# placa.net
KiCad netlist of a schematic drawn in EAGLE
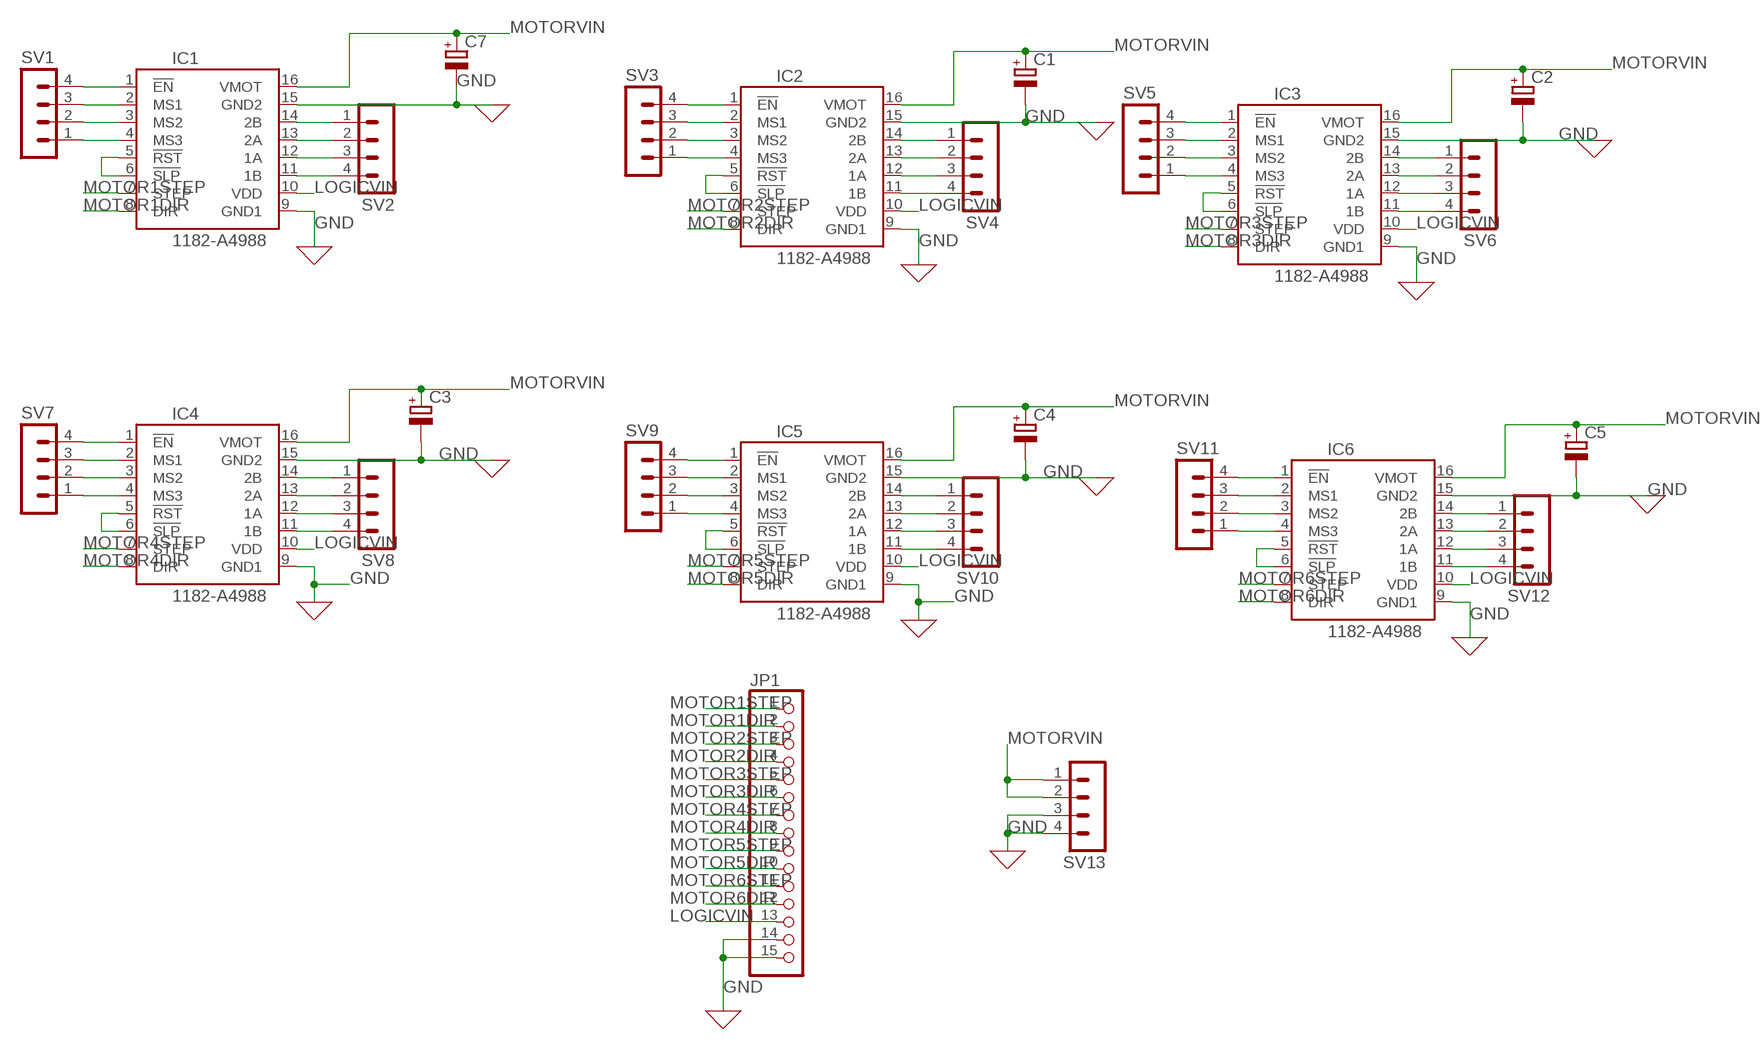
[diagram p0: schematic, sheet 1]

(export (version "E")
  (design (tool "Eeschema 10.0.6"))
  (components
    (comp (ref "C1")
      (value "CPOL-EUE2.5-7")
      (footprint "eagle-import:E2,5-7")
      (libsource (lib "eagle-import") (part "CPOL-EUE2.5-7"))
    )
    (comp (ref "C2")
      (value "CPOL-EUE2.5-7")
      (footprint "eagle-import:E2,5-7")
      (libsource (lib "eagle-import") (part "CPOL-EUE2.5-7"))
    )
    (comp (ref "C3")
      (value "CPOL-EUE2.5-7")
      (footprint "eagle-import:E2,5-7")
      (libsource (lib "eagle-import") (part "CPOL-EUE2.5-7"))
    )
    (comp (ref "C4")
      (value "CPOL-EUE2.5-7")
      (footprint "eagle-import:E2,5-7")
      (libsource (lib "eagle-import") (part "CPOL-EUE2.5-7"))
    )
    (comp (ref "C5")
      (value "CPOL-EUE2.5-7")
      (footprint "eagle-import:E2,5-7")
      (libsource (lib "eagle-import") (part "CPOL-EUE2.5-7"))
    )
    (comp (ref "C7")
      (value "CPOL-EUE2.5-7")
      (footprint "eagle-import:E2,5-7")
      (libsource (lib "eagle-import") (part "CPOL-EUE2.5-7"))
    )
    (comp (ref "IC1")
      (value "1182-A4988")
      (footprint "eagle-import:A4988")
      (libsource (lib "eagle-import") (part "1182-A4988"))
    )
    (comp (ref "IC2")
      (value "1182-A4988")
      (footprint "eagle-import:A4988")
      (libsource (lib "eagle-import") (part "1182-A4988"))
    )
    (comp (ref "IC3")
      (value "1182-A4988")
      (footprint "eagle-import:A4988")
      (libsource (lib "eagle-import") (part "1182-A4988"))
    )
    (comp (ref "IC4")
      (value "1182-A4988")
      (footprint "eagle-import:A4988")
      (libsource (lib "eagle-import") (part "1182-A4988"))
    )
    (comp (ref "IC5")
      (value "1182-A4988")
      (footprint "eagle-import:A4988")
      (libsource (lib "eagle-import") (part "1182-A4988"))
    )
    (comp (ref "IC6")
      (value "1182-A4988")
      (footprint "eagle-import:A4988")
      (libsource (lib "eagle-import") (part "1182-A4988"))
    )
    (comp (ref "JP1")
      (value "PINHD-1X15")
      (footprint "eagle-import:1X15")
      (libsource (lib "eagle-import") (part "PINHD-1X15"))
    )
    (comp (ref "SV1")
      (value "MA04-1")
      (footprint "eagle-import:MA04-1")
      (libsource (lib "eagle-import") (part "MA04-1"))
    )
    (comp (ref "SV2")
      (value "MA04-1")
      (footprint "eagle-import:MA04-1")
      (libsource (lib "eagle-import") (part "MA04-1"))
    )
    (comp (ref "SV3")
      (value "MA04-1")
      (footprint "eagle-import:MA04-1")
      (libsource (lib "eagle-import") (part "MA04-1"))
    )
    (comp (ref "SV4")
      (value "MA04-1")
      (footprint "eagle-import:MA04-1")
      (libsource (lib "eagle-import") (part "MA04-1"))
    )
    (comp (ref "SV5")
      (value "MA04-1")
      (footprint "eagle-import:MA04-1")
      (libsource (lib "eagle-import") (part "MA04-1"))
    )
    (comp (ref "SV6")
      (value "MA04-1")
      (footprint "eagle-import:MA04-1")
      (libsource (lib "eagle-import") (part "MA04-1"))
    )
    (comp (ref "SV7")
      (value "MA04-1")
      (footprint "eagle-import:MA04-1")
      (libsource (lib "eagle-import") (part "MA04-1"))
    )
    (comp (ref "SV8")
      (value "MA04-1")
      (footprint "eagle-import:MA04-1")
      (libsource (lib "eagle-import") (part "MA04-1"))
    )
    (comp (ref "SV9")
      (value "MA04-1")
      (footprint "eagle-import:MA04-1")
      (libsource (lib "eagle-import") (part "MA04-1"))
    )
    (comp (ref "SV10")
      (value "MA04-1")
      (footprint "eagle-import:MA04-1")
      (libsource (lib "eagle-import") (part "MA04-1"))
    )
    (comp (ref "SV11")
      (value "MA04-1")
      (footprint "eagle-import:MA04-1")
      (libsource (lib "eagle-import") (part "MA04-1"))
    )
    (comp (ref "SV12")
      (value "MA04-1")
      (footprint "eagle-import:MA04-1")
      (libsource (lib "eagle-import") (part "MA04-1"))
    )
    (comp (ref "SV13")
      (value "MA04-1")
      (footprint "eagle-import:MA04-1")
      (libsource (lib "eagle-import") (part "MA04-1"))
    )
  )
  (nets
    (net (code "1") (name "/LOGICVIN") (class "Default")
      (node (ref "IC1") (pin "10") (pinfunction "VDD_10") (pintype "power_in"))
      (node (ref "IC2") (pin "10") (pinfunction "VDD_10") (pintype "power_in"))
      (node (ref "IC3") (pin "10") (pinfunction "VDD_10") (pintype "power_in"))
      (node (ref "IC4") (pin "10") (pinfunction "VDD_10") (pintype "power_in"))
      (node (ref "IC5") (pin "10") (pinfunction "VDD_10") (pintype "power_in"))
      (node (ref "IC6") (pin "10") (pinfunction "VDD_10") (pintype "power_in"))
      (node (ref "JP1") (pin "13") (pinfunction "13_13") (pintype "passive"))
    )
    (net (code "2") (name "/MOTOR1DIR") (class "Default")
      (node (ref "IC1") (pin "8") (pinfunction "DIR_8") (pintype "input"))
      (node (ref "JP1") (pin "2") (pinfunction "2_2") (pintype "passive"))
    )
    (net (code "3") (name "/MOTOR1STEP") (class "Default")
      (node (ref "IC1") (pin "7") (pinfunction "STEP_7") (pintype "input"))
      (node (ref "JP1") (pin "1") (pinfunction "1_1") (pintype "passive"))
    )
    (net (code "4") (name "/MOTOR2DIR") (class "Default")
      (node (ref "IC2") (pin "8") (pinfunction "DIR_8") (pintype "input"))
      (node (ref "JP1") (pin "4") (pinfunction "4_4") (pintype "passive"))
    )
    (net (code "5") (name "/MOTOR2STEP") (class "Default")
      (node (ref "IC2") (pin "7") (pinfunction "STEP_7") (pintype "input"))
      (node (ref "JP1") (pin "3") (pinfunction "3_3") (pintype "passive"))
    )
    (net (code "6") (name "/MOTOR3DIR") (class "Default")
      (node (ref "IC3") (pin "8") (pinfunction "DIR_8") (pintype "input"))
      (node (ref "JP1") (pin "6") (pinfunction "6_6") (pintype "passive"))
    )
    (net (code "7") (name "/MOTOR3STEP") (class "Default")
      (node (ref "IC3") (pin "7") (pinfunction "STEP_7") (pintype "input"))
      (node (ref "JP1") (pin "5") (pinfunction "5_5") (pintype "passive"))
    )
    (net (code "8") (name "/MOTOR4DIR") (class "Default")
      (node (ref "IC4") (pin "8") (pinfunction "DIR_8") (pintype "input"))
      (node (ref "JP1") (pin "8") (pinfunction "8_8") (pintype "passive"))
    )
    (net (code "9") (name "/MOTOR4STEP") (class "Default")
      (node (ref "IC4") (pin "7") (pinfunction "STEP_7") (pintype "input"))
      (node (ref "JP1") (pin "7") (pinfunction "7_7") (pintype "passive"))
    )
    (net (code "10") (name "/MOTOR5DIR") (class "Default")
      (node (ref "IC5") (pin "8") (pinfunction "DIR_8") (pintype "input"))
      (node (ref "JP1") (pin "10") (pinfunction "10_10") (pintype "passive"))
    )
    (net (code "11") (name "/MOTOR5STEP") (class "Default")
      (node (ref "IC5") (pin "7") (pinfunction "STEP_7") (pintype "input"))
      (node (ref "JP1") (pin "9") (pinfunction "9_9") (pintype "passive"))
    )
    (net (code "12") (name "/MOTOR6DIR") (class "Default")
      (node (ref "IC6") (pin "8") (pinfunction "DIR_8") (pintype "input"))
      (node (ref "JP1") (pin "12") (pinfunction "12_12") (pintype "passive"))
    )
    (net (code "13") (name "/MOTOR6STEP") (class "Default")
      (node (ref "IC6") (pin "7") (pinfunction "STEP_7") (pintype "input"))
      (node (ref "JP1") (pin "11") (pinfunction "11_11") (pintype "passive"))
    )
    (net (code "14") (name "/MOTORVIN") (class "Default")
      (node (ref "C1") (pin "+") (pinfunction "+_+") (pintype "passive"))
      (node (ref "C2") (pin "+") (pinfunction "+_+") (pintype "passive"))
      (node (ref "C3") (pin "+") (pinfunction "+_+") (pintype "passive"))
      (node (ref "C4") (pin "+") (pinfunction "+_+") (pintype "passive"))
      (node (ref "C5") (pin "+") (pinfunction "+_+") (pintype "passive"))
      (node (ref "C7") (pin "+") (pinfunction "+_+") (pintype "passive"))
      (node (ref "IC1") (pin "16") (pinfunction "VMOT_16") (pintype "power_in"))
      (node (ref "IC2") (pin "16") (pinfunction "VMOT_16") (pintype "power_in"))
      (node (ref "IC3") (pin "16") (pinfunction "VMOT_16") (pintype "power_in"))
      (node (ref "IC4") (pin "16") (pinfunction "VMOT_16") (pintype "power_in"))
      (node (ref "IC5") (pin "16") (pinfunction "VMOT_16") (pintype "power_in"))
      (node (ref "IC6") (pin "16") (pinfunction "VMOT_16") (pintype "power_in"))
      (node (ref "SV13") (pin "1") (pinfunction "1_1") (pintype "passive"))
      (node (ref "SV13") (pin "2") (pinfunction "2_2") (pintype "passive"))
    )
    (net (code "15") (name "GND") (class "Default")
      (node (ref "C1") (pin "-") (pinfunction "-_-") (pintype "passive"))
      (node (ref "C2") (pin "-") (pinfunction "-_-") (pintype "passive"))
      (node (ref "C3") (pin "-") (pinfunction "-_-") (pintype "passive"))
      (node (ref "C4") (pin "-") (pinfunction "-_-") (pintype "passive"))
      (node (ref "C5") (pin "-") (pinfunction "-_-") (pintype "passive"))
      (node (ref "C7") (pin "-") (pinfunction "-_-") (pintype "passive"))
      (node (ref "IC1") (pin "15") (pinfunction "GND2_15") (pintype "power_in"))
      (node (ref "IC1") (pin "9") (pinfunction "GND1_9") (pintype "power_in"))
      (node (ref "IC2") (pin "15") (pinfunction "GND2_15") (pintype "power_in"))
      (node (ref "IC2") (pin "9") (pinfunction "GND1_9") (pintype "power_in"))
      (node (ref "IC3") (pin "15") (pinfunction "GND2_15") (pintype "power_in"))
      (node (ref "IC3") (pin "9") (pinfunction "GND1_9") (pintype "power_in"))
      (node (ref "IC4") (pin "15") (pinfunction "GND2_15") (pintype "power_in"))
      (node (ref "IC4") (pin "9") (pinfunction "GND1_9") (pintype "power_in"))
      (node (ref "IC5") (pin "15") (pinfunction "GND2_15") (pintype "power_in"))
      (node (ref "IC5") (pin "9") (pinfunction "GND1_9") (pintype "power_in"))
      (node (ref "IC6") (pin "15") (pinfunction "GND2_15") (pintype "power_in"))
      (node (ref "IC6") (pin "9") (pinfunction "GND1_9") (pintype "power_in"))
      (node (ref "JP1") (pin "14") (pinfunction "14_14") (pintype "passive"))
      (node (ref "JP1") (pin "15") (pinfunction "15_15") (pintype "passive"))
      (node (ref "SV13") (pin "3") (pinfunction "3_3") (pintype "passive"))
      (node (ref "SV13") (pin "4") (pinfunction "4_4") (pintype "passive"))
    )
    (net (code "16") (name "Net-(IC1-1A)") (class "Default")
      (node (ref "IC1") (pin "12") (pinfunction "1A_12") (pintype "output"))
      (node (ref "SV2") (pin "3") (pinfunction "3_3") (pintype "passive"))
    )
    (net (code "17") (name "Net-(IC1-1B)") (class "Default")
      (node (ref "IC1") (pin "11") (pinfunction "1B_11") (pintype "output"))
      (node (ref "SV2") (pin "4") (pinfunction "4_4") (pintype "passive"))
    )
    (net (code "18") (name "Net-(IC1-2A)") (class "Default")
      (node (ref "IC1") (pin "13") (pinfunction "2A_13") (pintype "output"))
      (node (ref "SV2") (pin "2") (pinfunction "2_2") (pintype "passive"))
    )
    (net (code "19") (name "Net-(IC1-2B)") (class "Default")
      (node (ref "IC1") (pin "14") (pinfunction "2B_14") (pintype "output"))
      (node (ref "SV2") (pin "1") (pinfunction "1_1") (pintype "passive"))
    )
    (net (code "20") (name "Net-(IC1-MS1)") (class "Default")
      (node (ref "IC1") (pin "2") (pinfunction "MS1_2") (pintype "passive"))
      (node (ref "SV1") (pin "3") (pinfunction "3_3") (pintype "passive"))
    )
    (net (code "21") (name "Net-(IC1-MS2)") (class "Default")
      (node (ref "IC1") (pin "3") (pinfunction "MS2_3") (pintype "passive"))
      (node (ref "SV1") (pin "2") (pinfunction "2_2") (pintype "passive"))
    )
    (net (code "22") (name "Net-(IC1-MS3)") (class "Default")
      (node (ref "IC1") (pin "4") (pinfunction "MS3_4") (pintype "passive"))
      (node (ref "SV1") (pin "1") (pinfunction "1_1") (pintype "passive"))
    )
    (net (code "23") (name "Net-(IC1-~{EN})") (class "Default")
      (node (ref "IC1") (pin "1") (pinfunction "~{EN}_1") (pintype "passive"))
      (node (ref "SV1") (pin "4") (pinfunction "4_4") (pintype "passive"))
    )
    (net (code "24") (name "Net-(IC1-~{RST})") (class "Default")
      (node (ref "IC1") (pin "5") (pinfunction "~{RST}_5") (pintype "passive"))
      (node (ref "IC1") (pin "6") (pinfunction "~{SLP}_6") (pintype "passive"))
    )
    (net (code "25") (name "Net-(IC2-1A)") (class "Default")
      (node (ref "IC2") (pin "12") (pinfunction "1A_12") (pintype "output"))
      (node (ref "SV4") (pin "3") (pinfunction "3_3") (pintype "passive"))
    )
    (net (code "26") (name "Net-(IC2-1B)") (class "Default")
      (node (ref "IC2") (pin "11") (pinfunction "1B_11") (pintype "output"))
      (node (ref "SV4") (pin "4") (pinfunction "4_4") (pintype "passive"))
    )
    (net (code "27") (name "Net-(IC2-2A)") (class "Default")
      (node (ref "IC2") (pin "13") (pinfunction "2A_13") (pintype "output"))
      (node (ref "SV4") (pin "2") (pinfunction "2_2") (pintype "passive"))
    )
    (net (code "28") (name "Net-(IC2-2B)") (class "Default")
      (node (ref "IC2") (pin "14") (pinfunction "2B_14") (pintype "output"))
      (node (ref "SV4") (pin "1") (pinfunction "1_1") (pintype "passive"))
    )
    (net (code "29") (name "Net-(IC2-MS1)") (class "Default")
      (node (ref "IC2") (pin "2") (pinfunction "MS1_2") (pintype "passive"))
      (node (ref "SV3") (pin "3") (pinfunction "3_3") (pintype "passive"))
    )
    (net (code "30") (name "Net-(IC2-MS2)") (class "Default")
      (node (ref "IC2") (pin "3") (pinfunction "MS2_3") (pintype "passive"))
      (node (ref "SV3") (pin "2") (pinfunction "2_2") (pintype "passive"))
    )
    (net (code "31") (name "Net-(IC2-MS3)") (class "Default")
      (node (ref "IC2") (pin "4") (pinfunction "MS3_4") (pintype "passive"))
      (node (ref "SV3") (pin "1") (pinfunction "1_1") (pintype "passive"))
    )
    (net (code "32") (name "Net-(IC2-~{EN})") (class "Default")
      (node (ref "IC2") (pin "1") (pinfunction "~{EN}_1") (pintype "passive"))
      (node (ref "SV3") (pin "4") (pinfunction "4_4") (pintype "passive"))
    )
    (net (code "33") (name "Net-(IC2-~{RST})") (class "Default")
      (node (ref "IC2") (pin "5") (pinfunction "~{RST}_5") (pintype "passive"))
      (node (ref "IC2") (pin "6") (pinfunction "~{SLP}_6") (pintype "passive"))
    )
    (net (code "34") (name "Net-(IC3-1A)") (class "Default")
      (node (ref "IC3") (pin "12") (pinfunction "1A_12") (pintype "output"))
      (node (ref "SV6") (pin "3") (pinfunction "3_3") (pintype "passive"))
    )
    (net (code "35") (name "Net-(IC3-1B)") (class "Default")
      (node (ref "IC3") (pin "11") (pinfunction "1B_11") (pintype "output"))
      (node (ref "SV6") (pin "4") (pinfunction "4_4") (pintype "passive"))
    )
    (net (code "36") (name "Net-(IC3-2A)") (class "Default")
      (node (ref "IC3") (pin "13") (pinfunction "2A_13") (pintype "output"))
      (node (ref "SV6") (pin "2") (pinfunction "2_2") (pintype "passive"))
    )
    (net (code "37") (name "Net-(IC3-2B)") (class "Default")
      (node (ref "IC3") (pin "14") (pinfunction "2B_14") (pintype "output"))
      (node (ref "SV6") (pin "1") (pinfunction "1_1") (pintype "passive"))
    )
    (net (code "38") (name "Net-(IC3-MS1)") (class "Default")
      (node (ref "IC3") (pin "2") (pinfunction "MS1_2") (pintype "passive"))
      (node (ref "SV5") (pin "3") (pinfunction "3_3") (pintype "passive"))
    )
    (net (code "39") (name "Net-(IC3-MS2)") (class "Default")
      (node (ref "IC3") (pin "3") (pinfunction "MS2_3") (pintype "passive"))
      (node (ref "SV5") (pin "2") (pinfunction "2_2") (pintype "passive"))
    )
    (net (code "40") (name "Net-(IC3-MS3)") (class "Default")
      (node (ref "IC3") (pin "4") (pinfunction "MS3_4") (pintype "passive"))
      (node (ref "SV5") (pin "1") (pinfunction "1_1") (pintype "passive"))
    )
    (net (code "41") (name "Net-(IC3-~{EN})") (class "Default")
      (node (ref "IC3") (pin "1") (pinfunction "~{EN}_1") (pintype "passive"))
      (node (ref "SV5") (pin "4") (pinfunction "4_4") (pintype "passive"))
    )
    (net (code "42") (name "Net-(IC3-~{RST})") (class "Default")
      (node (ref "IC3") (pin "5") (pinfunction "~{RST}_5") (pintype "passive"))
      (node (ref "IC3") (pin "6") (pinfunction "~{SLP}_6") (pintype "passive"))
    )
    (net (code "43") (name "Net-(IC4-1A)") (class "Default")
      (node (ref "IC4") (pin "12") (pinfunction "1A_12") (pintype "output"))
      (node (ref "SV8") (pin "3") (pinfunction "3_3") (pintype "passive"))
    )
    (net (code "44") (name "Net-(IC4-1B)") (class "Default")
      (node (ref "IC4") (pin "11") (pinfunction "1B_11") (pintype "output"))
      (node (ref "SV8") (pin "4") (pinfunction "4_4") (pintype "passive"))
    )
    (net (code "45") (name "Net-(IC4-2A)") (class "Default")
      (node (ref "IC4") (pin "13") (pinfunction "2A_13") (pintype "output"))
      (node (ref "SV8") (pin "2") (pinfunction "2_2") (pintype "passive"))
    )
    (net (code "46") (name "Net-(IC4-2B)") (class "Default")
      (node (ref "IC4") (pin "14") (pinfunction "2B_14") (pintype "output"))
      (node (ref "SV8") (pin "1") (pinfunction "1_1") (pintype "passive"))
    )
    (net (code "47") (name "Net-(IC4-MS1)") (class "Default")
      (node (ref "IC4") (pin "2") (pinfunction "MS1_2") (pintype "passive"))
      (node (ref "SV7") (pin "3") (pinfunction "3_3") (pintype "passive"))
    )
    (net (code "48") (name "Net-(IC4-MS2)") (class "Default")
      (node (ref "IC4") (pin "3") (pinfunction "MS2_3") (pintype "passive"))
      (node (ref "SV7") (pin "2") (pinfunction "2_2") (pintype "passive"))
    )
    (net (code "49") (name "Net-(IC4-MS3)") (class "Default")
      (node (ref "IC4") (pin "4") (pinfunction "MS3_4") (pintype "passive"))
      (node (ref "SV7") (pin "1") (pinfunction "1_1") (pintype "passive"))
    )
    (net (code "50") (name "Net-(IC4-~{EN})") (class "Default")
      (node (ref "IC4") (pin "1") (pinfunction "~{EN}_1") (pintype "passive"))
      (node (ref "SV7") (pin "4") (pinfunction "4_4") (pintype "passive"))
    )
    (net (code "51") (name "Net-(IC4-~{RST})") (class "Default")
      (node (ref "IC4") (pin "5") (pinfunction "~{RST}_5") (pintype "passive"))
      (node (ref "IC4") (pin "6") (pinfunction "~{SLP}_6") (pintype "passive"))
    )
    (net (code "52") (name "Net-(IC5-1A)") (class "Default")
      (node (ref "IC5") (pin "12") (pinfunction "1A_12") (pintype "output"))
      (node (ref "SV10") (pin "3") (pinfunction "3_3") (pintype "passive"))
    )
    (net (code "53") (name "Net-(IC5-1B)") (class "Default")
      (node (ref "IC5") (pin "11") (pinfunction "1B_11") (pintype "output"))
      (node (ref "SV10") (pin "4") (pinfunction "4_4") (pintype "passive"))
    )
    (net (code "54") (name "Net-(IC5-2A)") (class "Default")
      (node (ref "IC5") (pin "13") (pinfunction "2A_13") (pintype "output"))
      (node (ref "SV10") (pin "2") (pinfunction "2_2") (pintype "passive"))
    )
    (net (code "55") (name "Net-(IC5-2B)") (class "Default")
      (node (ref "IC5") (pin "14") (pinfunction "2B_14") (pintype "output"))
      (node (ref "SV10") (pin "1") (pinfunction "1_1") (pintype "passive"))
    )
    (net (code "56") (name "Net-(IC5-MS1)") (class "Default")
      (node (ref "IC5") (pin "2") (pinfunction "MS1_2") (pintype "passive"))
      (node (ref "SV9") (pin "3") (pinfunction "3_3") (pintype "passive"))
    )
    (net (code "57") (name "Net-(IC5-MS2)") (class "Default")
      (node (ref "IC5") (pin "3") (pinfunction "MS2_3") (pintype "passive"))
      (node (ref "SV9") (pin "2") (pinfunction "2_2") (pintype "passive"))
    )
    (net (code "58") (name "Net-(IC5-MS3)") (class "Default")
      (node (ref "IC5") (pin "4") (pinfunction "MS3_4") (pintype "passive"))
      (node (ref "SV9") (pin "1") (pinfunction "1_1") (pintype "passive"))
    )
    (net (code "59") (name "Net-(IC5-~{EN})") (class "Default")
      (node (ref "IC5") (pin "1") (pinfunction "~{EN}_1") (pintype "passive"))
      (node (ref "SV9") (pin "4") (pinfunction "4_4") (pintype "passive"))
    )
    (net (code "60") (name "Net-(IC5-~{RST})") (class "Default")
      (node (ref "IC5") (pin "5") (pinfunction "~{RST}_5") (pintype "passive"))
      (node (ref "IC5") (pin "6") (pinfunction "~{SLP}_6") (pintype "passive"))
    )
    (net (code "61") (name "Net-(IC6-1A)") (class "Default")
      (node (ref "IC6") (pin "12") (pinfunction "1A_12") (pintype "output"))
      (node (ref "SV12") (pin "3") (pinfunction "3_3") (pintype "passive"))
    )
    (net (code "62") (name "Net-(IC6-1B)") (class "Default")
      (node (ref "IC6") (pin "11") (pinfunction "1B_11") (pintype "output"))
      (node (ref "SV12") (pin "4") (pinfunction "4_4") (pintype "passive"))
    )
    (net (code "63") (name "Net-(IC6-2A)") (class "Default")
      (node (ref "IC6") (pin "13") (pinfunction "2A_13") (pintype "output"))
      (node (ref "SV12") (pin "2") (pinfunction "2_2") (pintype "passive"))
    )
    (net (code "64") (name "Net-(IC6-2B)") (class "Default")
      (node (ref "IC6") (pin "14") (pinfunction "2B_14") (pintype "output"))
      (node (ref "SV12") (pin "1") (pinfunction "1_1") (pintype "passive"))
    )
    (net (code "65") (name "Net-(IC6-MS1)") (class "Default")
      (node (ref "IC6") (pin "2") (pinfunction "MS1_2") (pintype "passive"))
      (node (ref "SV11") (pin "3") (pinfunction "3_3") (pintype "passive"))
    )
    (net (code "66") (name "Net-(IC6-MS2)") (class "Default")
      (node (ref "IC6") (pin "3") (pinfunction "MS2_3") (pintype "passive"))
      (node (ref "SV11") (pin "2") (pinfunction "2_2") (pintype "passive"))
    )
    (net (code "67") (name "Net-(IC6-MS3)") (class "Default")
      (node (ref "IC6") (pin "4") (pinfunction "MS3_4") (pintype "passive"))
      (node (ref "SV11") (pin "1") (pinfunction "1_1") (pintype "passive"))
    )
    (net (code "68") (name "Net-(IC6-~{EN})") (class "Default")
      (node (ref "IC6") (pin "1") (pinfunction "~{EN}_1") (pintype "passive"))
      (node (ref "SV11") (pin "4") (pinfunction "4_4") (pintype "passive"))
    )
    (net (code "69") (name "Net-(IC6-~{RST})") (class "Default")
      (node (ref "IC6") (pin "5") (pinfunction "~{RST}_5") (pintype "passive"))
      (node (ref "IC6") (pin "6") (pinfunction "~{SLP}_6") (pintype "passive"))
    )
  )
)
